# Motor-E1.net
KiCad netlist of a schematic drawn in Altium Designer
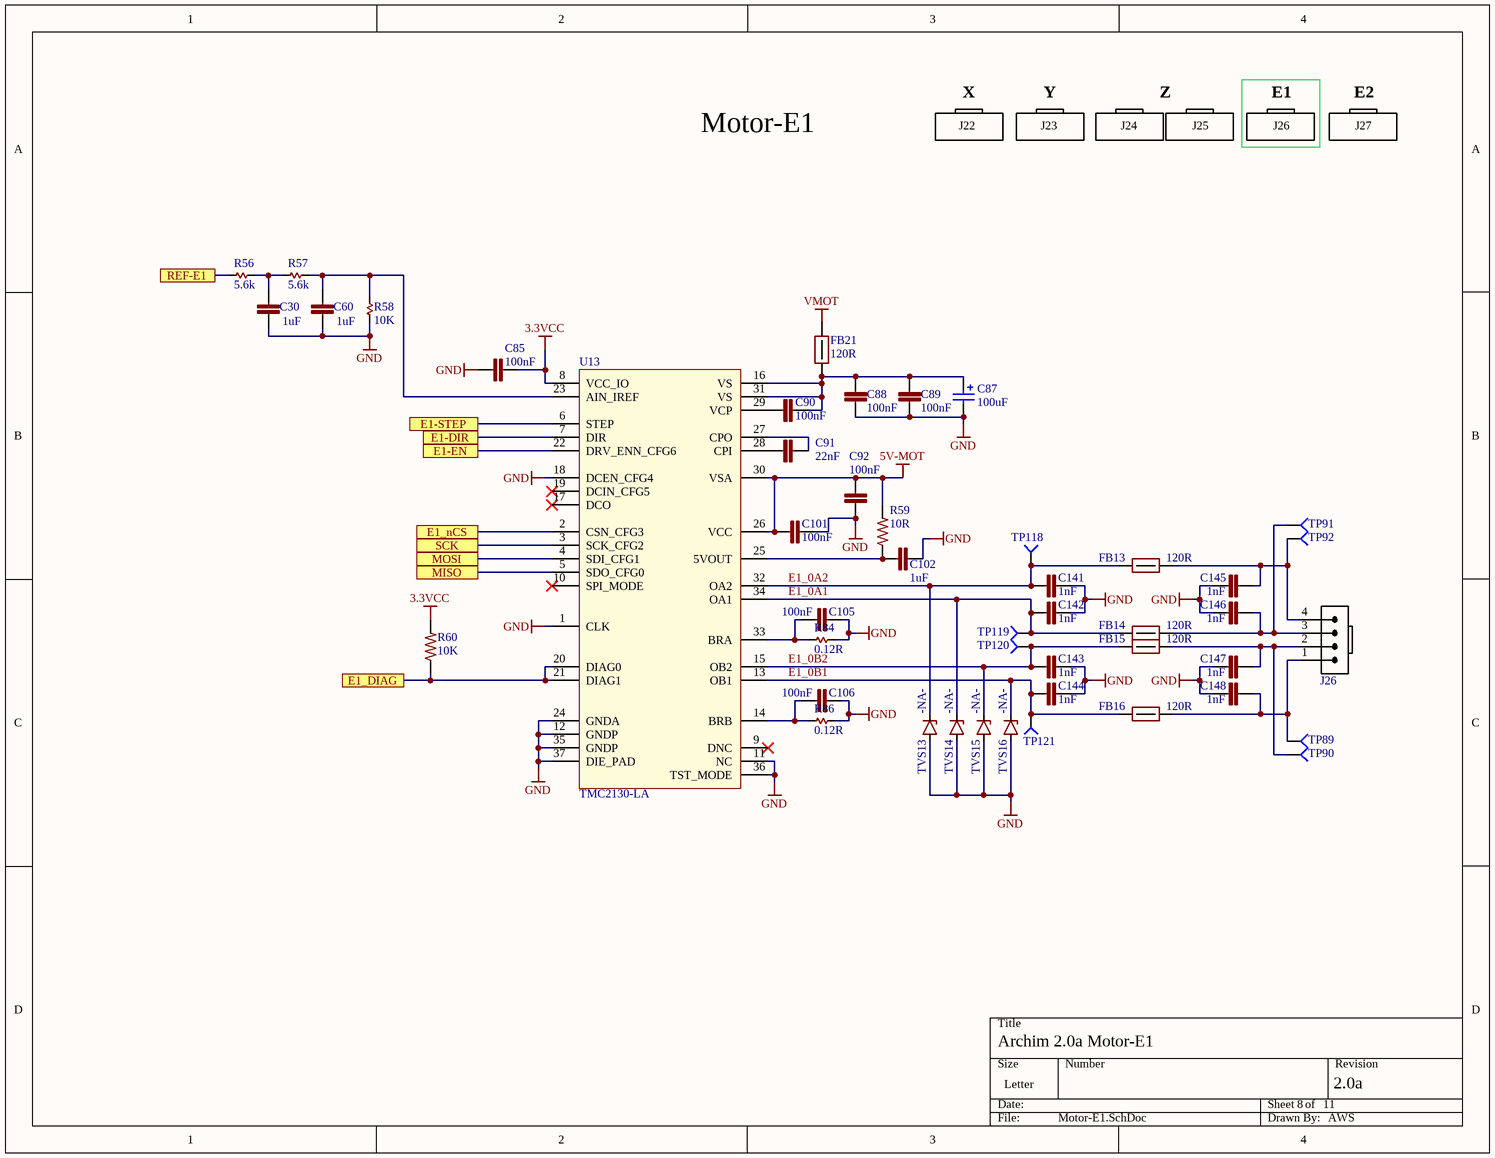
[diagram p0: Motor-E1.SchDoc]

(export (version "E")
  (design (tool "Eeschema 10.0.6"))
  (components
    (comp (ref "C30")
      (value "1uF")
      (footprint "C0402")
      (description "CAP CER 0402 1uF 6.3V 10% X5R")
      (fields (field (name "MANUFACTURER") "Murata") (field (name "PART") "1uF 6.3V X5R 0402"))
      (libsource (lib "3Delight") (part "GRM155R60J105KE19D"))
    )
    (comp (ref "C60")
      (value "1uF")
      (footprint "C0402")
      (description "CAP CER 0402 1uF 6.3V 10% X5R")
      (fields (field (name "MANUFACTURER") "Murata") (field (name "PART") "1uF 6.3V X5R 0402"))
      (libsource (lib "3Delight") (part "GRM155R60J105KE19D"))
    )
    (comp (ref "C85")
      (value "100nF")
      (footprint "C0402")
      (description "CAP CER 0402 100nF 16V 10% X7R")
      (fields (field (name "MANUFACTURER") "Murata") (field (name "PART") "0.1uF 16V X7R 0402"))
      (libsource (lib "3Delight") (part "GRM155R71C104KA88D"))
    )
    (comp (ref "C87")
      (value "100uF")
      (footprint "CAP-ELEC-063063077")
      (description "CAP ALUM 100UF 35V 20% SMD")
      (fields (field (name "MANUFACTURER") "Nichicon") (field (name "PART") "100uF 35V SMD Al-El"))
      (libsource (lib "3Delight") (part "UWT1V101MCL1GS"))
    )
    (comp (ref "C88")
      (value "100nF")
      (footprint "C0603")
      (description "CAP CER 0603 100nF 50V 10% X7R")
      (fields (field (name "MANUFACTURER") "Kemet") (field (name "PART") "100nF 50V X7R 0603"))
      (libsource (lib "") (part "C0603C104K5RACTU_1"))
    )
    (comp (ref "C89")
      (value "100nF")
      (footprint "C0603")
      (description "CAP CER 0603 100nF 50V 10% X7R")
      (fields (field (name "MANUFACTURER") "Kemet") (field (name "PART") "100nF 50V X7R 0603"))
      (libsource (lib "") (part "C0603C104K5RACTU_1"))
    )
    (comp (ref "C90")
      (value "100nF")
      (footprint "C0603")
      (description "CAP CER 0603 100nF 50V 10% X7R")
      (fields (field (name "MANUFACTURER") "Kemet") (field (name "PART") "100nF 50V X7R 0603"))
      (libsource (lib "3Delight") (part "C0603C104K5RACTU"))
    )
    (comp (ref "C91")
      (value "22nF")
      (footprint "C0402")
      (description "CAP CER 0402 22nF ±10% 50V X7R")
      (fields (field (name "MANUFACTURER") "YAGEO") (field (name "TOLERANCE") "+/- 10%"))
      (libsource (lib "3Delight") (part "GCM155R71H223KA55D"))
    )
    (comp (ref "C92")
      (value "100nF")
      (footprint "C0402")
      (description "CAP CER 0402 100nF 16V 10% X7R")
      (fields (field (name "MANUFACTURER") "Murata") (field (name "PART") "0.1uF 16V X7R 0402"))
      (libsource (lib "") (part "GRM155R71C104KA88D_1"))
    )
    (comp (ref "C101")
      (value "100nF")
      (footprint "C0402")
      (description "CAP CER 0402 100nF 16V 10% X7R")
      (fields (field (name "MANUFACTURER") "Murata") (field (name "PART") "0.1uF 16V X7R 0402"))
      (libsource (lib "3Delight") (part "GRM155R71C104KA88D"))
    )
    (comp (ref "C102")
      (value "1uF")
      (footprint "C0402")
      (description "CAP CER 0402 1uF 6.3V 10% X5R")
      (fields (field (name "MANUFACTURER") "Murata") (field (name "PART") "1uF 6.3V X5R 0402"))
      (libsource (lib "") (part "GRM155R60J105KE19D_1"))
    )
    (comp (ref "C105")
      (value "100nF")
      (footprint "C0603")
      (description "CAP CER 0603 100nF 50V 10% X7R")
      (fields (field (name "MANUFACTURER") "Kemet") (field (name "PART") "100nF 50V X7R 0603"))
      (libsource (lib "") (part "C0603C104K5RACTU_2"))
    )
    (comp (ref "C106")
      (value "100nF")
      (footprint "C0603")
      (description "CAP CER 0603 100nF 50V 10% X7R")
      (fields (field (name "MANUFACTURER") "Kemet") (field (name "PART") "100nF 50V X7R 0603"))
      (libsource (lib "") (part "C0603C104K5RACTU_2"))
    )
    (comp (ref "C141")
      (value "1nF")
      (footprint "C0402")
      (description "1000pF 50V Ceramic Capacitor X7R 0402 (1005 Metric) 0.039\" L x 0.020\" W (1.00mm x 0.50mm)")
      (fields (field (name "MANUFACTURER") "Murata") (field (name "PART") "1nF 50V X7R 0402"))
      (libsource (lib "3Delight") (part "CAP 1nF 50V 0402 X7R"))
    )
    (comp (ref "C142")
      (value "1nF")
      (footprint "C0402")
      (description "1000pF 50V Ceramic Capacitor X7R 0402 (1005 Metric) 0.039\" L x 0.020\" W (1.00mm x 0.50mm)")
      (fields (field (name "MANUFACTURER") "Murata") (field (name "PART") "1nF 50V X7R 0402"))
      (libsource (lib "3Delight") (part "CAP 1nF 50V 0402 X7R"))
    )
    (comp (ref "C143")
      (value "1nF")
      (footprint "C0402")
      (description "1000pF 50V Ceramic Capacitor X7R 0402 (1005 Metric) 0.039\" L x 0.020\" W (1.00mm x 0.50mm)")
      (fields (field (name "MANUFACTURER") "Murata") (field (name "PART") "1nF 50V X7R 0402"))
      (libsource (lib "3Delight") (part "CAP 1nF 50V 0402 X7R"))
    )
    (comp (ref "C144")
      (value "1nF")
      (footprint "C0402")
      (description "1000pF 50V Ceramic Capacitor X7R 0402 (1005 Metric) 0.039\" L x 0.020\" W (1.00mm x 0.50mm)")
      (fields (field (name "MANUFACTURER") "Murata") (field (name "PART") "1nF 50V X7R 0402"))
      (libsource (lib "3Delight") (part "CAP 1nF 50V 0402 X7R"))
    )
    (comp (ref "C145")
      (value "1nF")
      (footprint "C0402")
      (description "1000pF 50V Ceramic Capacitor X7R 0402 (1005 Metric) 0.039\" L x 0.020\" W (1.00mm x 0.50mm)")
      (fields (field (name "MANUFACTURER") "Murata") (field (name "PART") "1nF 50V X7R 0402"))
      (libsource (lib "3Delight") (part "CAP 1nF 50V 0402 X7R"))
    )
    (comp (ref "C146")
      (value "1nF")
      (footprint "C0402")
      (description "1000pF 50V Ceramic Capacitor X7R 0402 (1005 Metric) 0.039\" L x 0.020\" W (1.00mm x 0.50mm)")
      (fields (field (name "MANUFACTURER") "Murata") (field (name "PART") "1nF 50V X7R 0402"))
      (libsource (lib "3Delight") (part "CAP 1nF 50V 0402 X7R"))
    )
    (comp (ref "C147")
      (value "1nF")
      (footprint "C0402")
      (description "1000pF 50V Ceramic Capacitor X7R 0402 (1005 Metric) 0.039\" L x 0.020\" W (1.00mm x 0.50mm)")
      (fields (field (name "MANUFACTURER") "Murata") (field (name "PART") "1nF 50V X7R 0402"))
      (libsource (lib "3Delight") (part "CAP 1nF 50V 0402 X7R"))
    )
    (comp (ref "C148")
      (value "1nF")
      (footprint "C0402")
      (description "1000pF 50V Ceramic Capacitor X7R 0402 (1005 Metric) 0.039\" L x 0.020\" W (1.00mm x 0.50mm)")
      (fields (field (name "MANUFACTURER") "Murata") (field (name "PART") "1nF 50V X7R 0402"))
      (libsource (lib "3Delight") (part "CAP 1nF 50V 0402 X7R"))
    )
    (comp (ref "FB13")
      (value "120R")
      (footprint "FB0603")
      (description "FERRITE BEAD 120 OHM 0603 1LN")
      (fields (field (name "MANUFACTURER") "Samsung") (field (name "PART") "FERRITE 120R 3A 0603"))
      (libsource (lib "3Delight") (part "FERRITE 220R 2.5A 0603"))
    )
    (comp (ref "FB14")
      (value "120R")
      (footprint "FB0603")
      (description "FERRITE BEAD 120 OHM 0603 1LN")
      (fields (field (name "MANUFACTURER") "Samsung") (field (name "PART") "FERRITE 120R 3A 0603"))
      (libsource (lib "3Delight") (part "FERRITE 220R 2.5A 0603"))
    )
    (comp (ref "FB15")
      (value "120R")
      (footprint "FB0603")
      (description "FERRITE BEAD 120 OHM 0603 1LN")
      (fields (field (name "MANUFACTURER") "Samsung") (field (name "PART") "FERRITE 120R 3A 0603"))
      (libsource (lib "3Delight") (part "FERRITE 220R 2.5A 0603"))
    )
    (comp (ref "FB16")
      (value "120R")
      (footprint "FB0603")
      (description "FERRITE BEAD 120 OHM 0603 1LN")
      (fields (field (name "MANUFACTURER") "Samsung") (field (name "PART") "FERRITE 120R 3A 0603"))
      (libsource (lib "3Delight") (part "FERRITE 220R 2.5A 0603"))
    )
    (comp (ref "FB21")
      (value "120R")
      (footprint "FB0603")
      (description "FERRITE BEAD 120 OHM 0603 1LN")
      (fields (field (name "MANUFACTURER") "Samsung") (field (name "PART") "FERRITE 120R 3A 0603"))
      (libsource (lib "Inductors") (part "FERRITE 120R 3A 0603"))
    )
    (comp (ref "J26")
      (value "Molex 0705430038")
      (footprint "4POL254 PIN-IN-PASTE")
      (description "Molex 4 Pin Clip Connector - Pin In Paste footprint")
      (libsource (lib "Connectors") (part "Molex 0705430003 PIP"))
    )
    (comp (ref "R56")
      (value "5.6k")
      (footprint "R0402")
      (description "RES SMD 5.6K OHM 1% 1/16W 0402")
      (fields (field (name "MANUFACTURER") "YAGEO") (field (name "TOLERANCE") "1%"))
      (libsource (lib "Resistors") (part "5.6k 1% 0402"))
    )
    (comp (ref "R57")
      (value "5.6k")
      (footprint "R0402")
      (description "RES SMD 5.6K OHM 1% 1/16W 0402")
      (fields (field (name "MANUFACTURER") "YAGEO") (field (name "TOLERANCE") "1%"))
      (libsource (lib "Resistors") (part "5.6k 1% 0402"))
    )
    (comp (ref "R58")
      (value "10K")
      (footprint "R0402")
      (description "RES SMD 10K OHM 1% 1/16W 0402")
      (fields (field (name "MANUFACTURER") "Yageo") (field (name "PART") "10k 1% 0402"))
      (libsource (lib "Resistors") (part "10k 1% 0402"))
    )
    (comp (ref "R59")
      (value "10R")
      (footprint "R0402")
      (description "RES SMD 10 OHM 1% 1/16W 0402")
      (fields (field (name "MANUFACTURER") "Yageo") (field (name "TOLERANCE") "1%"))
      (libsource (lib "3Delight") (part "RC0402FR-0710RL"))
    )
    (comp (ref "R60")
      (value "10K")
      (footprint "R0402")
      (description "RES SMD 10K OHM 1% 1/16W 0402")
      (fields (field (name "MANUFACTURER") "Yageo") (field (name "PART") "10k 1% 0402"))
      (libsource (lib "3Delight") (part "RC0402FR-0710KP"))
    )
    (comp (ref "R84")
      (value "0.12R")
      (footprint "R1206")
      (description "RES 0.12 OHM 1% 1/2W 1206")
      (fields (field (name "TOLERANCE") "+/- 1%"))
      (libsource (lib "Resistors") (part "0.12R 1% 1206"))
    )
    (comp (ref "R86")
      (value "0.12R")
      (footprint "R1206")
      (description "RES 0.12 OHM 1% 1/2W 1206")
      (fields (field (name "TOLERANCE") "+/- 1%"))
      (libsource (lib "Resistors") (part "0.12R 1% 1206"))
    )
    (comp (ref "TP89")
      (value "TP4")
      (footprint "TP-2")
      (description "Socket")
      (libsource (lib "Archim") (part "Socket"))
    )
    (comp (ref "TP90")
      (value "TP4")
      (footprint "TP-2")
      (description "Socket")
      (libsource (lib "Archim") (part "Socket"))
    )
    (comp (ref "TP91")
      (value "TP4")
      (footprint "TP-2")
      (description "Socket")
      (libsource (lib "Archim") (part "Socket"))
    )
    (comp (ref "TP92")
      (value "TP4")
      (footprint "TP-2")
      (description "Socket")
      (libsource (lib "Archim") (part "Socket"))
    )
    (comp (ref "TP118")
      (value "TP4")
      (footprint "TP-2")
      (description "Socket")
      (libsource (lib "Archim") (part "Socket"))
    )
    (comp (ref "TP119")
      (value "TP4")
      (footprint "TP-2")
      (description "Socket")
      (libsource (lib "Archim") (part "Socket"))
    )
    (comp (ref "TP120")
      (value "TP4")
      (footprint "TP-2")
      (description "Socket")
      (libsource (lib "Archim") (part "Socket"))
    )
    (comp (ref "TP121")
      (value "TP4")
      (footprint "TP-2")
      (description "Socket")
      (libsource (lib "Archim") (part "Socket"))
    )
    (comp (ref "TVS13")
      (value "-NA-")
      (footprint "SMF")
      (description "TVS DIODE 30VWM 48.4VC SMF")
      (fields (field (name "MANUFACTURER") "Vishay") (field (name "PART") "TVS Diode 48.4VC"))
      (libsource (lib "3Delight") (part "TVS 30V SMF"))
    )
    (comp (ref "TVS14")
      (value "-NA-")
      (footprint "SMF")
      (description "TVS DIODE 30VWM 48.4VC SMF")
      (fields (field (name "MANUFACTURER") "Vishay") (field (name "PART") "TVS Diode 48.4VC"))
      (libsource (lib "3Delight") (part "TVS 30V SMF"))
    )
    (comp (ref "TVS15")
      (value "-NA-")
      (footprint "SMF")
      (description "TVS DIODE 30VWM 48.4VC SMF")
      (fields (field (name "MANUFACTURER") "Vishay") (field (name "PART") "TVS Diode 48.4VC"))
      (libsource (lib "3Delight") (part "TVS 30V SMF"))
    )
    (comp (ref "TVS16")
      (value "-NA-")
      (footprint "SMF")
      (description "TVS DIODE 30VWM 48.4VC SMF")
      (fields (field (name "MANUFACTURER") "Vishay") (field (name "PART") "TVS Diode 48.4VC"))
      (libsource (lib "3Delight") (part "TVS 30V SMF"))
    )
    (comp (ref "U13")
      (value "TMC2130-LA")
      (footprint "QFN36-50P500X600X900_HS-37N")
      (description "IC STEPPER MOTOR DVR SPI 36QFN")
      (fields (field (name "MANUFACTURER") "Trinamic") (field (name "PART") "TMC2130"))
      (libsource (lib "ICs-Motor Controller") (part "TMC2130-LA-T"))
    )
  )
  (nets
    (net (code "1") (name "/E1-DIR") (class "Default")
      (node (ref "U13") (pin "7") (pinfunction "DIR_7") (pintype "passive"))
    )
    (net (code "2") (name "/E1-EN") (class "Default")
      (node (ref "U13") (pin "22") (pinfunction "DRV_ENN_CFG6_22") (pintype "passive"))
    )
    (net (code "3") (name "/E1-STEP") (class "Default")
      (node (ref "U13") (pin "6") (pinfunction "STEP_6") (pintype "passive"))
    )
    (net (code "4") (name "/E1_0A1") (class "Default")
      (node (ref "C142") (pin "1") (pinfunction "1_1") (pintype "passive"))
      (node (ref "FB14") (pin "1") (pinfunction "1_1") (pintype "passive"))
      (node (ref "TP119") (pin "1") (pinfunction "1_1") (pintype "passive"))
      (node (ref "TVS14") (pin "K") (pinfunction "K_K") (pintype "passive"))
      (node (ref "U13") (pin "34") (pinfunction "OA1_34") (pintype "passive"))
    )
    (net (code "5") (name "/E1_0A2") (class "Default")
      (node (ref "C141") (pin "1") (pinfunction "1_1") (pintype "passive"))
      (node (ref "FB13") (pin "1") (pinfunction "1_1") (pintype "passive"))
      (node (ref "TP118") (pin "1") (pinfunction "1_1") (pintype "passive"))
      (node (ref "TVS13") (pin "K") (pinfunction "K_K") (pintype "passive"))
      (node (ref "U13") (pin "32") (pinfunction "OA2_32") (pintype "passive"))
    )
    (net (code "6") (name "/E1_0B1") (class "Default")
      (node (ref "C144") (pin "1") (pinfunction "1_1") (pintype "passive"))
      (node (ref "FB16") (pin "1") (pinfunction "1_1") (pintype "passive"))
      (node (ref "TP121") (pin "1") (pinfunction "1_1") (pintype "passive"))
      (node (ref "TVS16") (pin "K") (pinfunction "K_K") (pintype "passive"))
      (node (ref "U13") (pin "13") (pinfunction "OB1_13") (pintype "passive"))
    )
    (net (code "7") (name "/E1_0B2") (class "Default")
      (node (ref "C143") (pin "1") (pinfunction "1_1") (pintype "passive"))
      (node (ref "FB15") (pin "1") (pinfunction "1_1") (pintype "passive"))
      (node (ref "TP120") (pin "1") (pinfunction "1_1") (pintype "passive"))
      (node (ref "TVS15") (pin "K") (pinfunction "K_K") (pintype "passive"))
      (node (ref "U13") (pin "15") (pinfunction "OB2_15") (pintype "passive"))
    )
    (net (code "8") (name "/E1_DIAG") (class "Default")
      (node (ref "R60") (pin "1") (pinfunction "1_1") (pintype "passive"))
      (node (ref "U13") (pin "20") (pinfunction "DIAG0_20") (pintype "passive"))
      (node (ref "U13") (pin "21") (pinfunction "DIAG1_21") (pintype "passive"))
    )
    (net (code "9") (name "/E1_nCS") (class "Default")
      (node (ref "U13") (pin "2") (pinfunction "CSN_CFG3_2") (pintype "passive"))
    )
    (net (code "10") (name "/MISO") (class "Default")
      (node (ref "U13") (pin "5") (pinfunction "SDO_CFG0_5") (pintype "passive"))
    )
    (net (code "11") (name "/MOSI") (class "Default")
      (node (ref "U13") (pin "4") (pinfunction "SDI_CFG1_4") (pintype "passive"))
    )
    (net (code "12") (name "/REF-E1") (class "Default")
      (node (ref "R56") (pin "1") (pinfunction "1_1") (pintype "passive"))
    )
    (net (code "13") (name "/SCK") (class "Default")
      (node (ref "U13") (pin "3") (pinfunction "SCK_CFG2_3") (pintype "passive"))
    )
    (net (code "14") (name "3.3VCC") (class "Default")
      (node (ref "C85") (pin "1") (pinfunction "1_1") (pintype "passive"))
      (node (ref "R60") (pin "2") (pinfunction "2_2") (pintype "passive"))
      (node (ref "U13") (pin "8") (pinfunction "VCC_IO_8") (pintype "passive"))
    )
    (net (code "15") (name "5V-MOT") (class "Default")
      (node (ref "C101") (pin "2") (pinfunction "2_2") (pintype "passive"))
      (node (ref "C92") (pin "2") (pinfunction "2_2") (pintype "passive"))
      (node (ref "R59") (pin "2") (pinfunction "2_2") (pintype "passive"))
      (node (ref "U13") (pin "26") (pinfunction "VCC_26") (pintype "passive"))
      (node (ref "U13") (pin "30") (pinfunction "VSA_30") (pintype "passive"))
    )
    (net (code "16") (name "GND") (class "Default")
      (node (ref "C101") (pin "1") (pinfunction "1_1") (pintype "passive"))
      (node (ref "C102") (pin "2") (pinfunction "2_2") (pintype "passive"))
      (node (ref "C105") (pin "1") (pinfunction "1_1") (pintype "passive"))
      (node (ref "C106") (pin "1") (pinfunction "1_1") (pintype "passive"))
      (node (ref "C141") (pin "2") (pinfunction "2_2") (pintype "passive"))
      (node (ref "C142") (pin "2") (pinfunction "2_2") (pintype "passive"))
      (node (ref "C143") (pin "2") (pinfunction "2_2") (pintype "passive"))
      (node (ref "C144") (pin "2") (pinfunction "2_2") (pintype "passive"))
      (node (ref "C145") (pin "1") (pinfunction "1_1") (pintype "passive"))
      (node (ref "C146") (pin "1") (pinfunction "1_1") (pintype "passive"))
      (node (ref "C147") (pin "1") (pinfunction "1_1") (pintype "passive"))
      (node (ref "C148") (pin "1") (pinfunction "1_1") (pintype "passive"))
      (node (ref "C30") (pin "2") (pinfunction "2_2") (pintype "passive"))
      (node (ref "C60") (pin "2") (pinfunction "2_2") (pintype "passive"))
      (node (ref "C85") (pin "2") (pinfunction "2_2") (pintype "passive"))
      (node (ref "C87") (pin "2") (pinfunction "2_2") (pintype "passive"))
      (node (ref "C88") (pin "1") (pinfunction "1_1") (pintype "passive"))
      (node (ref "C89") (pin "1") (pinfunction "1_1") (pintype "passive"))
      (node (ref "C92") (pin "1") (pinfunction "1_1") (pintype "passive"))
      (node (ref "R58") (pin "1") (pinfunction "1_1") (pintype "passive"))
      (node (ref "R84") (pin "2") (pinfunction "2_2") (pintype "passive"))
      (node (ref "R86") (pin "2") (pinfunction "2_2") (pintype "passive"))
      (node (ref "TVS13") (pin "A") (pinfunction "A_A") (pintype "passive"))
      (node (ref "TVS14") (pin "A") (pinfunction "A_A") (pintype "passive"))
      (node (ref "TVS15") (pin "A") (pinfunction "A_A") (pintype "passive"))
      (node (ref "TVS16") (pin "A") (pinfunction "A_A") (pintype "passive"))
      (node (ref "U13") (pin "1") (pinfunction "CLK_1") (pintype "passive"))
      (node (ref "U13") (pin "11") (pinfunction "NC_11") (pintype "passive"))
      (node (ref "U13") (pin "12") (pinfunction "GNDP_12") (pintype "passive"))
      (node (ref "U13") (pin "18") (pinfunction "DCEN_CFG4_18") (pintype "passive"))
      (node (ref "U13") (pin "24") (pinfunction "GNDA_24") (pintype "passive"))
      (node (ref "U13") (pin "35") (pinfunction "GNDP_35") (pintype "passive"))
      (node (ref "U13") (pin "36") (pinfunction "TST_MODE_36") (pintype "passive"))
      (node (ref "U13") (pin "37") (pinfunction "DIE_PAD_37") (pintype "passive"))
    )
    (net (code "17") (name "Net-(C30-Pad1)") (class "Default")
      (node (ref "C30") (pin "1") (pinfunction "1_1") (pintype "passive"))
      (node (ref "R56") (pin "2") (pinfunction "2_2") (pintype "passive"))
      (node (ref "R57") (pin "1") (pinfunction "1_1") (pintype "passive"))
    )
    (net (code "18") (name "Net-(C87-Pad1)") (class "Default")
      (node (ref "C87") (pin "1") (pinfunction "1_1") (pintype "passive"))
      (node (ref "C88") (pin "2") (pinfunction "2_2") (pintype "passive"))
      (node (ref "C89") (pin "2") (pinfunction "2_2") (pintype "passive"))
      (node (ref "C90") (pin "2") (pinfunction "2_2") (pintype "passive"))
      (node (ref "FB21") (pin "1") (pinfunction "1_1") (pintype "passive"))
      (node (ref "U13") (pin "16") (pinfunction "VS_16") (pintype "passive"))
      (node (ref "U13") (pin "31") (pinfunction "VS_31") (pintype "passive"))
    )
    (net (code "19") (name "Net-(C145-Pad2)") (class "Default")
      (node (ref "C145") (pin "2") (pinfunction "2_2") (pintype "passive"))
      (node (ref "FB13") (pin "2") (pinfunction "2_2") (pintype "passive"))
      (node (ref "J26") (pin "4") (pinfunction "4_4") (pintype "passive"))
      (node (ref "TP92") (pin "1") (pinfunction "1_1") (pintype "passive"))
    )
    (net (code "20") (name "Net-(C146-Pad2)") (class "Default")
      (node (ref "C146") (pin "2") (pinfunction "2_2") (pintype "passive"))
      (node (ref "FB14") (pin "2") (pinfunction "2_2") (pintype "passive"))
      (node (ref "J26") (pin "3") (pinfunction "3_3") (pintype "passive"))
      (node (ref "TP91") (pin "1") (pinfunction "1_1") (pintype "passive"))
    )
    (net (code "21") (name "Net-(C147-Pad2)") (class "Default")
      (node (ref "C147") (pin "2") (pinfunction "2_2") (pintype "passive"))
      (node (ref "FB15") (pin "2") (pinfunction "2_2") (pintype "passive"))
      (node (ref "J26") (pin "2") (pinfunction "2_2") (pintype "passive"))
      (node (ref "TP90") (pin "1") (pinfunction "1_1") (pintype "passive"))
    )
    (net (code "22") (name "Net-(C148-Pad2)") (class "Default")
      (node (ref "C148") (pin "2") (pinfunction "2_2") (pintype "passive"))
      (node (ref "FB16") (pin "2") (pinfunction "2_2") (pintype "passive"))
      (node (ref "J26") (pin "1") (pinfunction "1_1") (pintype "passive"))
      (node (ref "TP89") (pin "1") (pinfunction "1_1") (pintype "passive"))
    )
    (net (code "23") (name "Net-(U13-5VOUT)") (class "Default")
      (node (ref "C102") (pin "1") (pinfunction "1_1") (pintype "passive"))
      (node (ref "R59") (pin "1") (pinfunction "1_1") (pintype "passive"))
      (node (ref "U13") (pin "25") (pinfunction "5VOUT_25") (pintype "passive"))
    )
    (net (code "24") (name "Net-(U13-AIN_IREF)") (class "Default")
      (node (ref "C60") (pin "1") (pinfunction "1_1") (pintype "passive"))
      (node (ref "R57") (pin "2") (pinfunction "2_2") (pintype "passive"))
      (node (ref "R58") (pin "2") (pinfunction "2_2") (pintype "passive"))
      (node (ref "U13") (pin "23") (pinfunction "AIN_IREF_23") (pintype "passive"))
    )
    (net (code "25") (name "Net-(U13-BRA)") (class "Default")
      (node (ref "C105") (pin "2") (pinfunction "2_2") (pintype "passive"))
      (node (ref "R84") (pin "1") (pinfunction "1_1") (pintype "passive"))
      (node (ref "U13") (pin "33") (pinfunction "BRA_33") (pintype "passive"))
    )
    (net (code "26") (name "Net-(U13-BRB)") (class "Default")
      (node (ref "C106") (pin "2") (pinfunction "2_2") (pintype "passive"))
      (node (ref "R86") (pin "1") (pinfunction "1_1") (pintype "passive"))
      (node (ref "U13") (pin "14") (pinfunction "BRB_14") (pintype "passive"))
    )
    (net (code "27") (name "Net-(U13-CPI)") (class "Default")
      (node (ref "C91") (pin "1") (pinfunction "1_1") (pintype "passive"))
      (node (ref "U13") (pin "28") (pinfunction "CPI_28") (pintype "passive"))
    )
    (net (code "28") (name "Net-(U13-CPO)") (class "Default")
      (node (ref "C91") (pin "2") (pinfunction "2_2") (pintype "passive"))
      (node (ref "U13") (pin "27") (pinfunction "CPO_27") (pintype "passive"))
    )
    (net (code "29") (name "Net-(U13-VCP)") (class "Default")
      (node (ref "C90") (pin "1") (pinfunction "1_1") (pintype "passive"))
      (node (ref "U13") (pin "29") (pinfunction "VCP_29") (pintype "passive"))
    )
    (net (code "30") (name "VMOT") (class "Default")
      (node (ref "FB21") (pin "2") (pinfunction "2_2") (pintype "passive"))
    )
    (net (code "31") (name "unconnected-(U13-DCIN_CFG5-Pad19)") (class "Default")
      (node (ref "U13") (pin "19") (pinfunction "DCIN_CFG5_19") (pintype "passive+no_connect"))
    )
    (net (code "32") (name "unconnected-(U13-DCO-Pad17)") (class "Default")
      (node (ref "U13") (pin "17") (pinfunction "DCO_17") (pintype "passive+no_connect"))
    )
    (net (code "33") (name "unconnected-(U13-DNC-Pad9)") (class "Default")
      (node (ref "U13") (pin "9") (pinfunction "DNC_9") (pintype "passive+no_connect"))
    )
    (net (code "34") (name "unconnected-(U13-SPI_MODE-Pad10)") (class "Default")
      (node (ref "U13") (pin "10") (pinfunction "SPI_MODE_10") (pintype "passive+no_connect"))
    )
  )
)
